# FMC_connector.net
KiCad netlist of a schematic drawn in Altium Designer
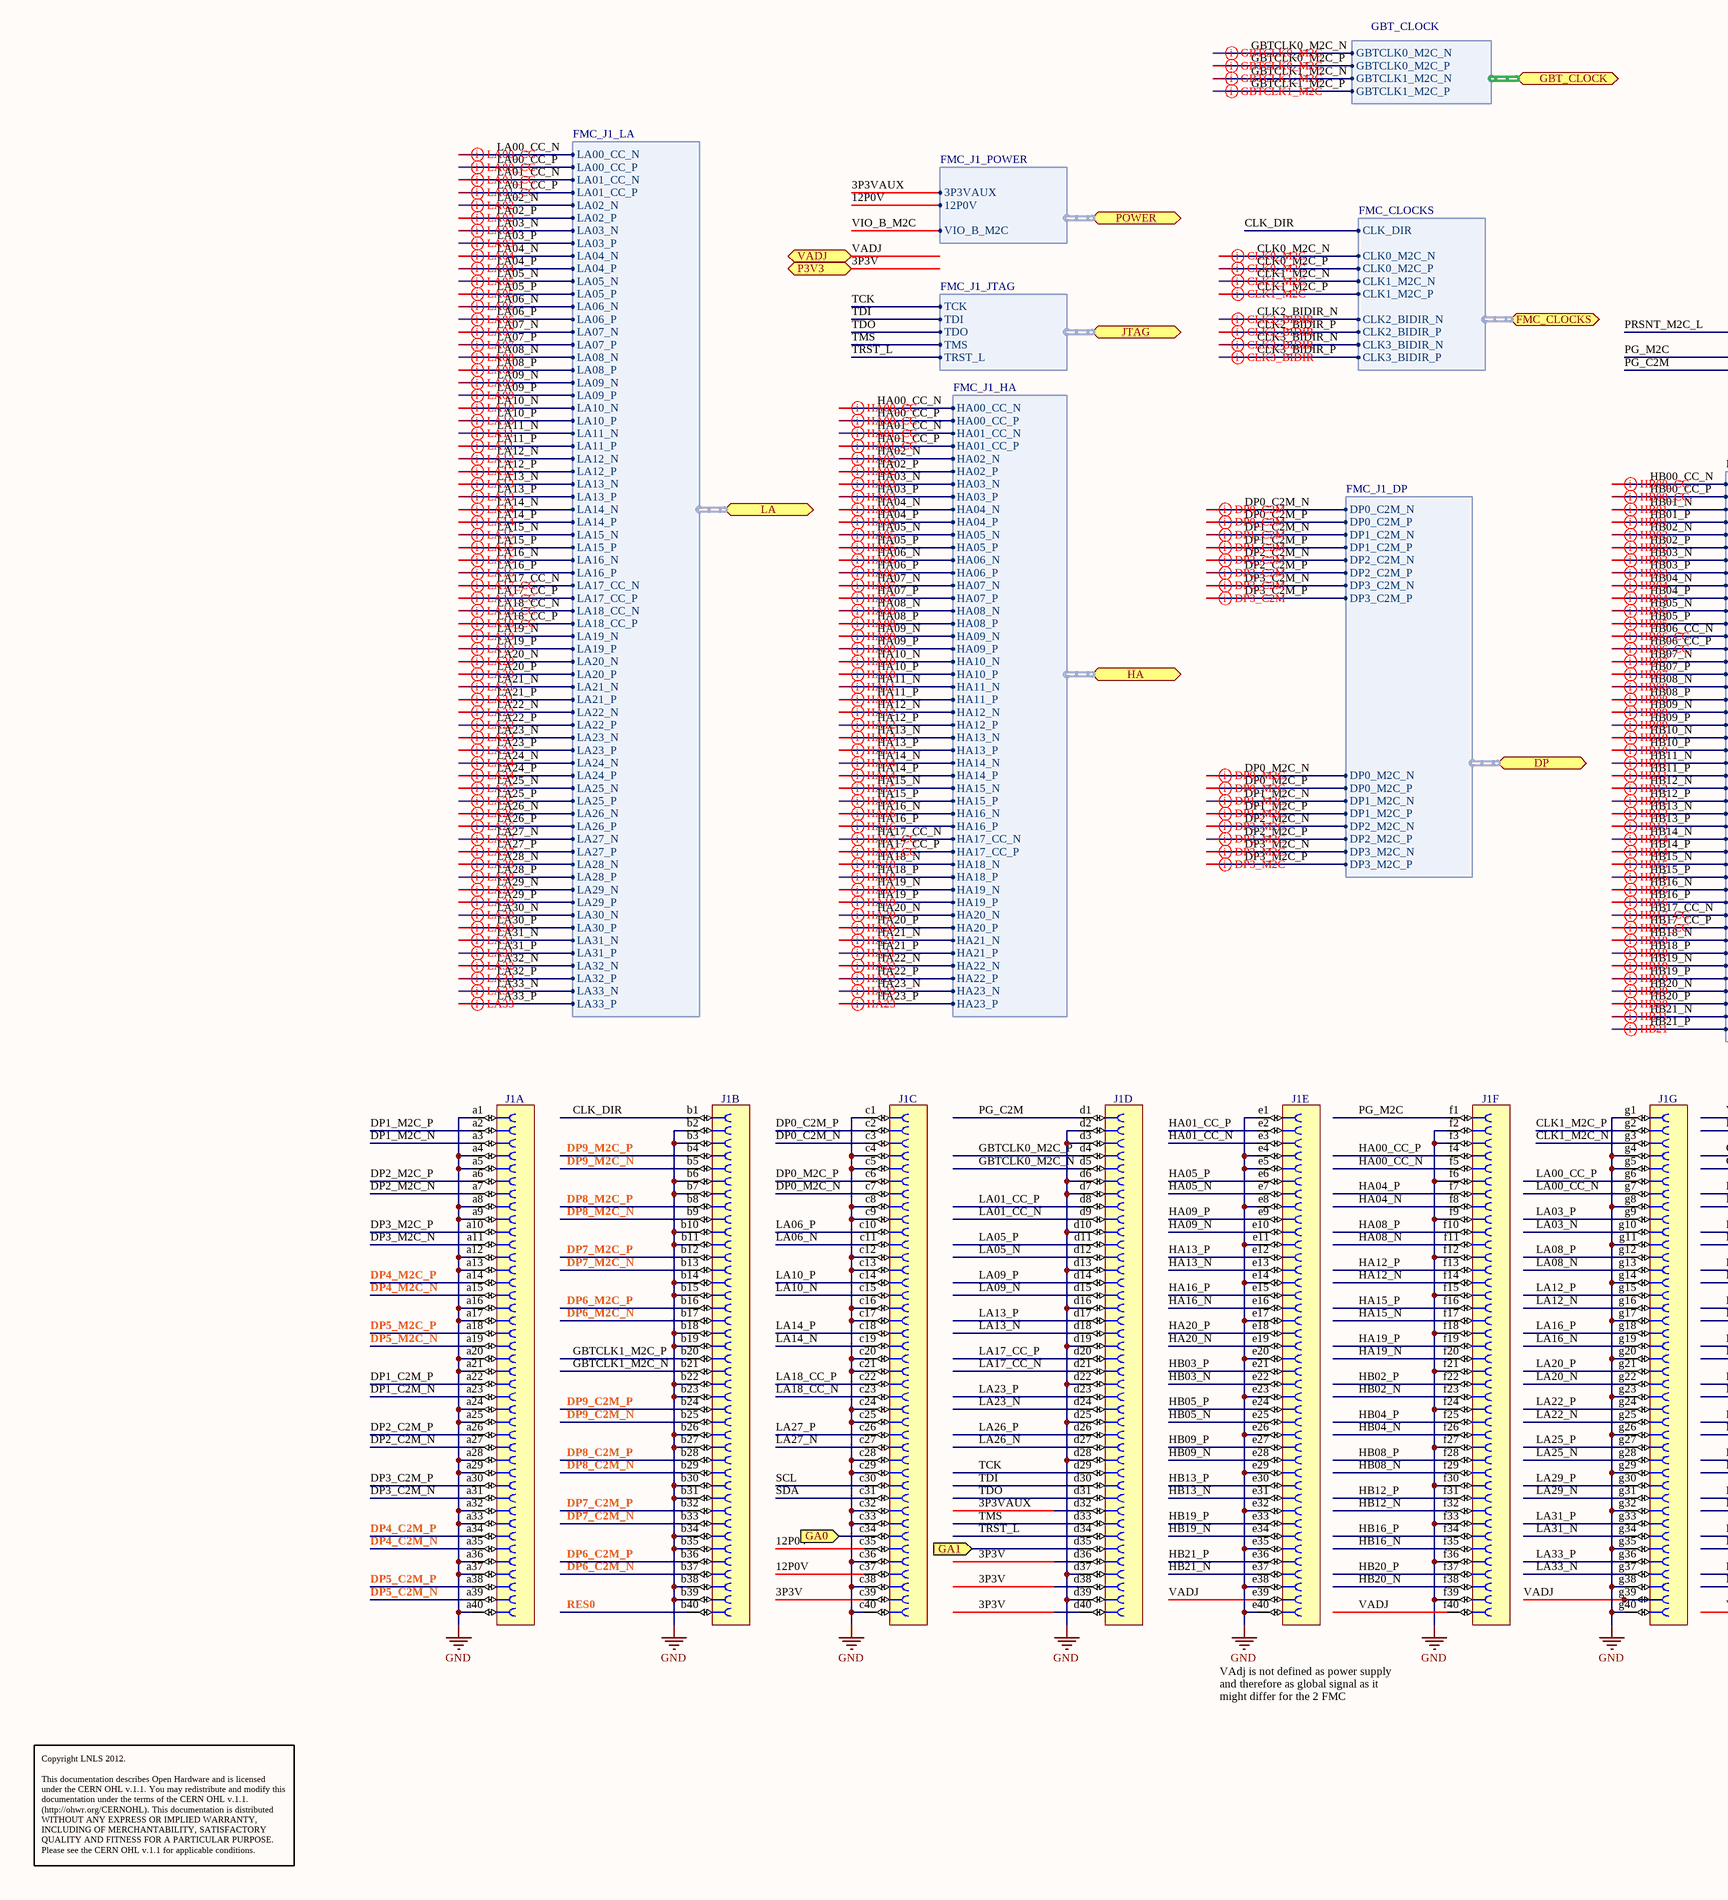
[diagram p0: FMC_connector.SchDoc, left]
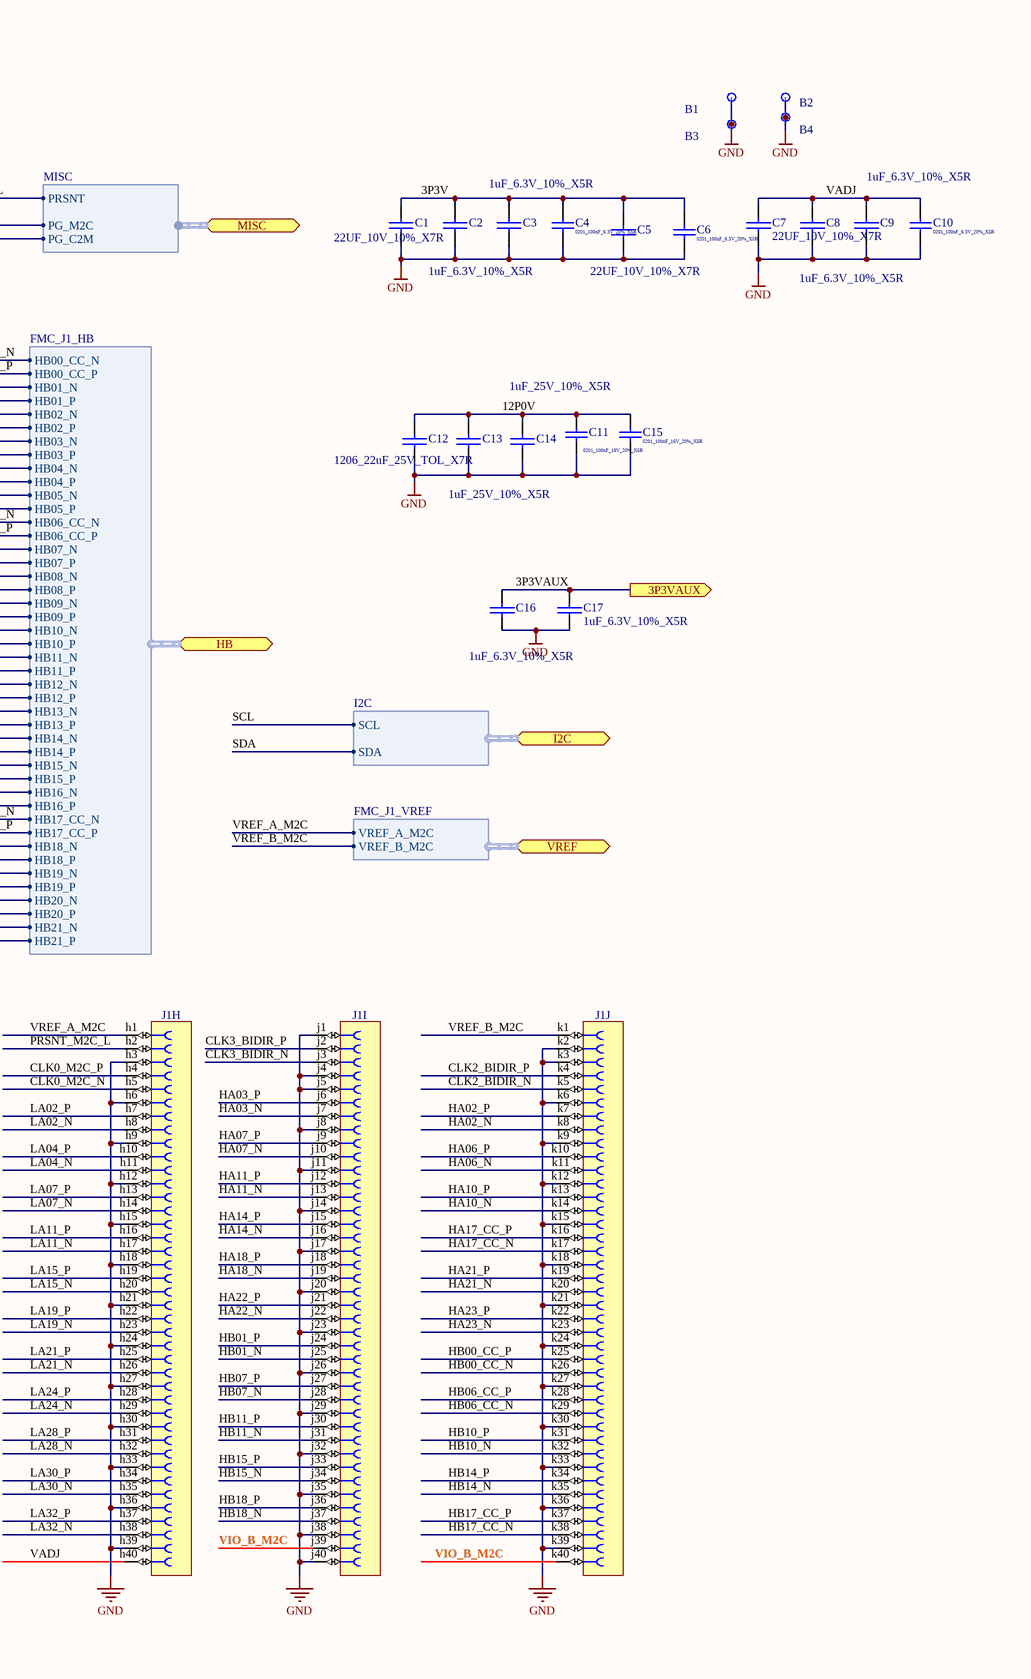
[diagram p1: FMC_connector.SchDoc, right]

(export (version "E")
  (design (tool "Eeschema 10.0.6"))
  (components
    (comp (ref "B1")
      (value "Plated Hole")
      (footprint "MTG270_500")
      (description "Single Terminal Socket")
      (fields (field (name "PART NUMBER") "PLATED_HOLE2.7_PAD5.0") (field (name "AUTHOR") "CERN DEM JMW"))
      (libsource (lib "Eletro-mechanical") (part "Single Terminal Socket"))
    )
    (comp (ref "B2")
      (value "Plated Hole")
      (footprint "MTG270_500")
      (description "Single Terminal Socket")
      (fields (field (name "PART NUMBER") "PLATED_HOLE2.7_PAD5.0") (field (name "AUTHOR") "CERN DEM JMW"))
      (libsource (lib "Eletro-mechanical") (part "Single Terminal Socket"))
    )
    (comp (ref "B3")
      (value "Plated Hole")
      (footprint "MTG270_500")
      (description "Single Terminal Socket")
      (fields (field (name "PART NUMBER") "PLATED_HOLE2.7_PAD5.0") (field (name "AUTHOR") "CERN DEM JMW"))
      (libsource (lib "Eletro-mechanical") (part "Single Terminal Socket"))
    )
    (comp (ref "B4")
      (value "Plated Hole")
      (footprint "MTG270_500")
      (description "Single Terminal Socket")
      (fields (field (name "PART NUMBER") "PLATED_HOLE2.7_PAD5.0") (field (name "AUTHOR") "CERN DEM JMW"))
      (libsource (lib "Eletro-mechanical") (part "Single Terminal Socket"))
    )
    (comp (ref "C1")
      (value "22UF_10V_10%_X7R")
      (footprint "1206C")
      (description "Capacitor SMD")
      (libsource (lib "LIBRARY_SCH") (part "CAP_SMD_1206"))
    )
    (comp (ref "C2")
      (value "1uF_6.3V_10%_X5R")
      (footprint "0603C")
      (description "Capacitor SMD")
      (libsource (lib "LIBRARY_SCH") (part "CAP_SMD_0603"))
    )
    (comp (ref "C3")
      (value "1uF_6.3V_10%_X5R")
      (footprint "0603C")
      (description "Capacitor SMD")
      (libsource (lib "LIBRARY_SCH") (part "CAP_SMD_0603"))
    )
    (comp (ref "C4")
      (value "0201_100nF_6.3V_20%_X5R")
      (footprint "CAPC0603X33N")
      (fields (field (name "PART NUMBER") "Ceramic_0201"))
      (libsource (lib "Capacitors") (part "Capacitor"))
    )
    (comp (ref "C5")
      (value "22UF_10V_10%_X7R")
      (footprint "1206C")
      (description "Capacitor SMD")
      (libsource (lib "LIBRARY_SCH") (part "CAP_SMD_1206"))
    )
    (comp (ref "C6")
      (value "0201_100nF_6.3V_20%_X5R")
      (footprint "CAPC0603X33N")
      (fields (field (name "PART NUMBER") "Ceramic_0201"))
      (libsource (lib "Capacitors") (part "Capacitor"))
    )
    (comp (ref "C7")
      (value "22UF_10V_10%_X7R")
      (footprint "1206C")
      (description "Capacitor SMD")
      (libsource (lib "LIBRARY_SCH") (part "CAP_SMD_1206"))
    )
    (comp (ref "C8")
      (value "1uF_6.3V_10%_X5R")
      (footprint "0603C")
      (description "Capacitor SMD")
      (libsource (lib "LIBRARY_SCH") (part "CAP_SMD_0603"))
    )
    (comp (ref "C9")
      (value "1uF_6.3V_10%_X5R")
      (footprint "0603C")
      (description "Capacitor SMD")
      (libsource (lib "LIBRARY_SCH") (part "CAP_SMD_0603"))
    )
    (comp (ref "C10")
      (value "0201_100nF_6.3V_20%_X5R")
      (footprint "CAPC0603X33N")
      (fields (field (name "PART NUMBER") "Ceramic_0201"))
      (libsource (lib "Capacitors") (part "Capacitor"))
    )
    (comp (ref "C11")
      (value "0201_100nF_16V_20%_X5R")
      (footprint "CAPC0603X33N")
      (fields (field (name "PART NUMBER") "Ceramic_0201"))
      (libsource (lib "Capacitors") (part "Capacitor"))
    )
    (comp (ref "C12")
      (value "1206_22uF_25V_TOL_X7R")
      (footprint "1206C")
      (description "Capacitor SMD")
      (libsource (lib "LIBRARY_SCH") (part "CAP_SMD_1206"))
    )
    (comp (ref "C13")
      (value "1uF_25V_10%_X5R")
      (footprint "0603C")
      (description "Capacitor SMD")
      (libsource (lib "LIBRARY_SCH") (part "CAP_SMD_0603"))
    )
    (comp (ref "C14")
      (value "1uF_25V_10%_X5R")
      (footprint "0603C")
      (description "Capacitor SMD")
      (libsource (lib "LIBRARY_SCH") (part "CAP_SMD_0603"))
    )
    (comp (ref "C15")
      (value "0201_100nF_16V_20%_X5R")
      (footprint "CAPC0603X33N")
      (fields (field (name "PART NUMBER") "Ceramic_0201"))
      (libsource (lib "Capacitors") (part "Capacitor"))
    )
    (comp (ref "C16")
      (value "1uF_6.3V_10%_X5R")
      (footprint "0603C")
      (description "Capacitor SMD")
      (libsource (lib "LIBRARY_SCH") (part "CAP_SMD_0603"))
    )
    (comp (ref "C17")
      (value "1uF_6.3V_10%_X5R")
      (footprint "0603C")
      (description "Capacitor SMD")
      (libsource (lib "LIBRARY_SCH") (part "CAP_SMD_0603"))
    )
    (comp (ref "J1")
      (value "VITA 57")
      (footprint "SAMTEC_ASP-134486-01")
      (description "Connector VITA 57, 400 Female contacts in 10 row abcdefghj")
      (fields
        (field (name "PART NUMBER") "SAMTEC_ASP-134486-01")
        (field (name "MANUFACTURER") "SAMTEC")
        (field (name "AUTHOR") "CERN DEM JLC")
      )
      (libsource (lib "Connectors") (part "Connector VITA 57 400 Female (abcdefghjk)"))
    )
  )
  (nets
    (net (code "12") (name "/3P3V") (class "Default")
      (node (ref "C1") (pin "1") (pinfunction "1_1") (pintype "passive"))
      (node (ref "C2") (pin "1") (pinfunction "1_1") (pintype "passive"))
      (node (ref "C3") (pin "1") (pinfunction "1_1") (pintype "passive"))
      (node (ref "C4") (pin "2") (pinfunction "2_2") (pintype "passive"))
      (node (ref "C5") (pin "1") (pinfunction "1_1") (pintype "passive"))
      (node (ref "C6") (pin "2") (pinfunction "2_2") (pintype "passive"))
      (node (ref "J1") (pin "c39") (pinfunction "c39_c39") (pintype "bidirectional"))
      (node (ref "J1") (pin "d36") (pinfunction "d36_d36") (pintype "bidirectional"))
      (node (ref "J1") (pin "d38") (pinfunction "d38_d38") (pintype "bidirectional"))
      (node (ref "J1") (pin "d40") (pinfunction "d40_d40") (pintype "bidirectional"))
    )
    (net (code "13") (name "/3P3VAUX") (class "Default")
      (node (ref "C16") (pin "1") (pinfunction "1_1") (pintype "passive"))
      (node (ref "C17") (pin "1") (pinfunction "1_1") (pintype "passive"))
      (node (ref "J1") (pin "d32") (pinfunction "d32_d32") (pintype "bidirectional"))
    )
    (net (code "14") (name "/12P0V") (class "Default")
      (node (ref "C11") (pin "2") (pinfunction "2_2") (pintype "passive"))
      (node (ref "C12") (pin "1") (pinfunction "1_1") (pintype "passive"))
      (node (ref "C13") (pin "1") (pinfunction "1_1") (pintype "passive"))
      (node (ref "C14") (pin "1") (pinfunction "1_1") (pintype "passive"))
      (node (ref "C15") (pin "2") (pinfunction "2_2") (pintype "passive"))
      (node (ref "J1") (pin "c35") (pinfunction "c35_c35") (pintype "bidirectional"))
      (node (ref "J1") (pin "c37") (pinfunction "c37_c37") (pintype "bidirectional"))
    )
    (net (code "15") (name "/CLK0_M2C_N") (class "Default")
      (node (ref "J1") (pin "h5") (pinfunction "h5_h5") (pintype "bidirectional"))
    )
    (net (code "16") (name "/CLK0_M2C_P") (class "Default")
      (node (ref "J1") (pin "h4") (pinfunction "h4_h4") (pintype "bidirectional"))
    )
    (net (code "17") (name "/CLK1_M2C_N") (class "Default")
      (node (ref "J1") (pin "g3") (pinfunction "g3_g3") (pintype "bidirectional"))
    )
    (net (code "18") (name "/CLK1_M2C_P") (class "Default")
      (node (ref "J1") (pin "g2") (pinfunction "g2_g2") (pintype "bidirectional"))
    )
    (net (code "19") (name "/CLK2_BIDIR_N") (class "Default")
      (node (ref "J1") (pin "k5") (pinfunction "k5_k5") (pintype "bidirectional"))
    )
    (net (code "20") (name "/CLK2_BIDIR_P") (class "Default")
      (node (ref "J1") (pin "k4") (pinfunction "k4_k4") (pintype "bidirectional"))
    )
    (net (code "21") (name "/CLK3_BIDIR_N") (class "Default")
      (node (ref "J1") (pin "j3") (pinfunction "j3_j3") (pintype "bidirectional"))
    )
    (net (code "22") (name "/CLK3_BIDIR_P") (class "Default")
      (node (ref "J1") (pin "j2") (pinfunction "j2_j2") (pintype "bidirectional"))
    )
    (net (code "23") (name "/CLK_DIR") (class "Default")
      (node (ref "J1") (pin "b1") (pinfunction "b1_b1") (pintype "bidirectional"))
    )
    (net (code "24") (name "/DP0_C2M_N") (class "Default")
      (node (ref "J1") (pin "c3") (pinfunction "c3_c3") (pintype "bidirectional"))
    )
    (net (code "25") (name "/DP0_C2M_P") (class "Default")
      (node (ref "J1") (pin "c2") (pinfunction "c2_c2") (pintype "bidirectional"))
    )
    (net (code "26") (name "/DP0_M2C_N") (class "Default")
      (node (ref "J1") (pin "c7") (pinfunction "c7_c7") (pintype "bidirectional"))
    )
    (net (code "27") (name "/DP0_M2C_P") (class "Default")
      (node (ref "J1") (pin "c6") (pinfunction "c6_c6") (pintype "bidirectional"))
    )
    (net (code "28") (name "/DP1_C2M_N") (class "Default")
      (node (ref "J1") (pin "a23") (pinfunction "a23_a23") (pintype "bidirectional"))
    )
    (net (code "29") (name "/DP1_C2M_P") (class "Default")
      (node (ref "J1") (pin "a22") (pinfunction "a22_a22") (pintype "bidirectional"))
    )
    (net (code "30") (name "/DP1_M2C_N") (class "Default")
      (node (ref "J1") (pin "a3") (pinfunction "a3_a3") (pintype "bidirectional"))
    )
    (net (code "31") (name "/DP1_M2C_P") (class "Default")
      (node (ref "J1") (pin "a2") (pinfunction "a2_a2") (pintype "bidirectional"))
    )
    (net (code "32") (name "/DP2_C2M_N") (class "Default")
      (node (ref "J1") (pin "a27") (pinfunction "a27_a27") (pintype "bidirectional"))
    )
    (net (code "33") (name "/DP2_C2M_P") (class "Default")
      (node (ref "J1") (pin "a26") (pinfunction "a26_a26") (pintype "bidirectional"))
    )
    (net (code "34") (name "/DP2_M2C_N") (class "Default")
      (node (ref "J1") (pin "a7") (pinfunction "a7_a7") (pintype "bidirectional"))
    )
    (net (code "35") (name "/DP2_M2C_P") (class "Default")
      (node (ref "J1") (pin "a6") (pinfunction "a6_a6") (pintype "bidirectional"))
    )
    (net (code "36") (name "/DP3_C2M_N") (class "Default")
      (node (ref "J1") (pin "a31") (pinfunction "a31_a31") (pintype "bidirectional"))
    )
    (net (code "37") (name "/DP3_C2M_P") (class "Default")
      (node (ref "J1") (pin "a30") (pinfunction "a30_a30") (pintype "bidirectional"))
    )
    (net (code "38") (name "/DP3_M2C_N") (class "Default")
      (node (ref "J1") (pin "a11") (pinfunction "a11_a11") (pintype "bidirectional"))
    )
    (net (code "39") (name "/DP3_M2C_P") (class "Default")
      (node (ref "J1") (pin "a10") (pinfunction "a10_a10") (pintype "bidirectional"))
    )
    (net (code "40") (name "/GA0") (class "Default")
      (node (ref "J1") (pin "c34") (pinfunction "c34_c34") (pintype "bidirectional"))
    )
    (net (code "41") (name "/GA1") (class "Default")
      (node (ref "J1") (pin "d35") (pinfunction "d35_d35") (pintype "bidirectional"))
    )
    (net (code "42") (name "/GBTCLK0_M2C_N") (class "Default")
      (node (ref "J1") (pin "d5") (pinfunction "d5_d5") (pintype "bidirectional"))
    )
    (net (code "43") (name "/GBTCLK0_M2C_P") (class "Default")
      (node (ref "J1") (pin "d4") (pinfunction "d4_d4") (pintype "bidirectional"))
    )
    (net (code "44") (name "/GBTCLK1_M2C_N") (class "Default")
      (node (ref "J1") (pin "b21") (pinfunction "b21_b21") (pintype "bidirectional"))
    )
    (net (code "45") (name "/GBTCLK1_M2C_P") (class "Default")
      (node (ref "J1") (pin "b20") (pinfunction "b20_b20") (pintype "bidirectional"))
    )
    (net (code "46") (name "/HA00_CC_N") (class "Default")
      (node (ref "J1") (pin "f5") (pinfunction "f5_f5") (pintype "bidirectional"))
    )
    (net (code "47") (name "/HA00_CC_P") (class "Default")
      (node (ref "J1") (pin "f4") (pinfunction "f4_f4") (pintype "bidirectional"))
    )
    (net (code "48") (name "/HA01_CC_N") (class "Default")
      (node (ref "J1") (pin "e3") (pinfunction "e3_e3") (pintype "bidirectional"))
    )
    (net (code "49") (name "/HA01_CC_P") (class "Default")
      (node (ref "J1") (pin "e2") (pinfunction "e2_e2") (pintype "bidirectional"))
    )
    (net (code "50") (name "/HA02_N") (class "Default")
      (node (ref "J1") (pin "k8") (pinfunction "k8_k8") (pintype "bidirectional"))
    )
    (net (code "51") (name "/HA02_P") (class "Default")
      (node (ref "J1") (pin "k7") (pinfunction "k7_k7") (pintype "bidirectional"))
    )
    (net (code "52") (name "/HA03_N") (class "Default")
      (node (ref "J1") (pin "j7") (pinfunction "j7_j7") (pintype "bidirectional"))
    )
    (net (code "53") (name "/HA03_P") (class "Default")
      (node (ref "J1") (pin "j6") (pinfunction "j6_j6") (pintype "bidirectional"))
    )
    (net (code "54") (name "/HA04_N") (class "Default")
      (node (ref "J1") (pin "f8") (pinfunction "f8_f8") (pintype "bidirectional"))
    )
    (net (code "55") (name "/HA04_P") (class "Default")
      (node (ref "J1") (pin "f7") (pinfunction "f7_f7") (pintype "bidirectional"))
    )
    (net (code "56") (name "/HA05_N") (class "Default")
      (node (ref "J1") (pin "e7") (pinfunction "e7_e7") (pintype "bidirectional"))
    )
    (net (code "57") (name "/HA05_P") (class "Default")
      (node (ref "J1") (pin "e6") (pinfunction "e6_e6") (pintype "bidirectional"))
    )
    (net (code "58") (name "/HA06_N") (class "Default")
      (node (ref "J1") (pin "k11") (pinfunction "k11_k11") (pintype "bidirectional"))
    )
    (net (code "59") (name "/HA06_P") (class "Default")
      (node (ref "J1") (pin "k10") (pinfunction "k10_k10") (pintype "bidirectional"))
    )
    (net (code "60") (name "/HA07_N") (class "Default")
      (node (ref "J1") (pin "j10") (pinfunction "j10_j10") (pintype "bidirectional"))
    )
    (net (code "61") (name "/HA07_P") (class "Default")
      (node (ref "J1") (pin "j9") (pinfunction "j9_j9") (pintype "bidirectional"))
    )
    (net (code "62") (name "/HA08_N") (class "Default")
      (node (ref "J1") (pin "f11") (pinfunction "f11_f11") (pintype "bidirectional"))
    )
    (net (code "63") (name "/HA08_P") (class "Default")
      (node (ref "J1") (pin "f10") (pinfunction "f10_f10") (pintype "bidirectional"))
    )
    (net (code "64") (name "/HA09_N") (class "Default")
      (node (ref "J1") (pin "e10") (pinfunction "e10_e10") (pintype "bidirectional"))
    )
    (net (code "65") (name "/HA09_P") (class "Default")
      (node (ref "J1") (pin "e9") (pinfunction "e9_e9") (pintype "bidirectional"))
    )
    (net (code "66") (name "/HA10_N") (class "Default")
      (node (ref "J1") (pin "k14") (pinfunction "k14_k14") (pintype "bidirectional"))
    )
    (net (code "67") (name "/HA10_P") (class "Default")
      (node (ref "J1") (pin "k13") (pinfunction "k13_k13") (pintype "bidirectional"))
    )
    (net (code "68") (name "/HA11_N") (class "Default")
      (node (ref "J1") (pin "j13") (pinfunction "j13_j13") (pintype "bidirectional"))
    )
    (net (code "69") (name "/HA11_P") (class "Default")
      (node (ref "J1") (pin "j12") (pinfunction "j12_j12") (pintype "bidirectional"))
    )
    (net (code "70") (name "/HA12_N") (class "Default")
      (node (ref "J1") (pin "f14") (pinfunction "f14_f14") (pintype "bidirectional"))
    )
    (net (code "71") (name "/HA12_P") (class "Default")
      (node (ref "J1") (pin "f13") (pinfunction "f13_f13") (pintype "bidirectional"))
    )
    (net (code "72") (name "/HA13_N") (class "Default")
      (node (ref "J1") (pin "e13") (pinfunction "e13_e13") (pintype "bidirectional"))
    )
    (net (code "73") (name "/HA13_P") (class "Default")
      (node (ref "J1") (pin "e12") (pinfunction "e12_e12") (pintype "bidirectional"))
    )
    (net (code "74") (name "/HA14_N") (class "Default")
      (node (ref "J1") (pin "j16") (pinfunction "j16_j16") (pintype "bidirectional"))
    )
    (net (code "75") (name "/HA14_P") (class "Default")
      (node (ref "J1") (pin "j15") (pinfunction "j15_j15") (pintype "bidirectional"))
    )
    (net (code "76") (name "/HA15_N") (class "Default")
      (node (ref "J1") (pin "f17") (pinfunction "f17_f17") (pintype "bidirectional"))
    )
    (net (code "77") (name "/HA15_P") (class "Default")
      (node (ref "J1") (pin "f16") (pinfunction "f16_f16") (pintype "bidirectional"))
    )
    (net (code "78") (name "/HA16_N") (class "Default")
      (node (ref "J1") (pin "e16") (pinfunction "e16_e16") (pintype "bidirectional"))
    )
    (net (code "79") (name "/HA16_P") (class "Default")
      (node (ref "J1") (pin "e15") (pinfunction "e15_e15") (pintype "bidirectional"))
    )
    (net (code "80") (name "/HA17_CC_N") (class "Default")
      (node (ref "J1") (pin "k17") (pinfunction "k17_k17") (pintype "bidirectional"))
    )
    (net (code "81") (name "/HA17_CC_P") (class "Default")
      (node (ref "J1") (pin "k16") (pinfunction "k16_k16") (pintype "bidirectional"))
    )
    (net (code "82") (name "/HA18_N") (class "Default")
      (node (ref "J1") (pin "j19") (pinfunction "j19_j19") (pintype "bidirectional"))
    )
    (net (code "83") (name "/HA18_P") (class "Default")
      (node (ref "J1") (pin "j18") (pinfunction "j18_j18") (pintype "bidirectional"))
    )
    (net (code "84") (name "/HA19_N") (class "Default")
      (node (ref "J1") (pin "f20") (pinfunction "f20_f20") (pintype "bidirectional"))
    )
    (net (code "85") (name "/HA19_P") (class "Default")
      (node (ref "J1") (pin "f19") (pinfunction "f19_f19") (pintype "bidirectional"))
    )
    (net (code "86") (name "/HA20_N") (class "Default")
      (node (ref "J1") (pin "e19") (pinfunction "e19_e19") (pintype "bidirectional"))
    )
    (net (code "87") (name "/HA20_P") (class "Default")
      (node (ref "J1") (pin "e18") (pinfunction "e18_e18") (pintype "bidirectional"))
    )
    (net (code "88") (name "/HA21_N") (class "Default")
      (node (ref "J1") (pin "k20") (pinfunction "k20_k20") (pintype "bidirectional"))
    )
    (net (code "89") (name "/HA21_P") (class "Default")
      (node (ref "J1") (pin "k19") (pinfunction "k19_k19") (pintype "bidirectional"))
    )
    (net (code "90") (name "/HA22_N") (class "Default")
      (node (ref "J1") (pin "j22") (pinfunction "j22_j22") (pintype "bidirectional"))
    )
    (net (code "91") (name "/HA22_P") (class "Default")
      (node (ref "J1") (pin "j21") (pinfunction "j21_j21") (pintype "bidirectional"))
    )
    (net (code "92") (name "/HA23_N") (class "Default")
      (node (ref "J1") (pin "k23") (pinfunction "k23_k23") (pintype "bidirectional"))
    )
    (net (code "93") (name "/HA23_P") (class "Default")
      (node (ref "J1") (pin "k22") (pinfunction "k22_k22") (pintype "bidirectional"))
    )
    (net (code "94") (name "/HB00_CC_N") (class "Default")
      (node (ref "J1") (pin "k26") (pinfunction "k26_k26") (pintype "bidirectional"))
    )
    (net (code "95") (name "/HB00_CC_P") (class "Default")
      (node (ref "J1") (pin "k25") (pinfunction "k25_k25") (pintype "bidirectional"))
    )
    (net (code "96") (name "/HB01_N") (class "Default")
      (node (ref "J1") (pin "j25") (pinfunction "j25_j25") (pintype "bidirectional"))
    )
    (net (code "97") (name "/HB01_P") (class "Default")
      (node (ref "J1") (pin "j24") (pinfunction "j24_j24") (pintype "bidirectional"))
    )
    (net (code "98") (name "/HB02_N") (class "Default")
      (node (ref "J1") (pin "f23") (pinfunction "f23_f23") (pintype "bidirectional"))
    )
    (net (code "99") (name "/HB02_P") (class "Default")
      (node (ref "J1") (pin "f22") (pinfunction "f22_f22") (pintype "bidirectional"))
    )
    (net (code "100") (name "/HB03_N") (class "Default")
      (node (ref "J1") (pin "e22") (pinfunction "e22_e22") (pintype "bidirectional"))
    )
    (net (code "101") (name "/HB03_P") (class "Default")
      (node (ref "J1") (pin "e21") (pinfunction "e21_e21") (pintype "bidirectional"))
    )
    (net (code "102") (name "/HB04_N") (class "Default")
      (node (ref "J1") (pin "f26") (pinfunction "f26_f26") (pintype "bidirectional"))
    )
    (net (code "103") (name "/HB04_P") (class "Default")
      (node (ref "J1") (pin "f25") (pinfunction "f25_f25") (pintype "bidirectional"))
    )
    (net (code "104") (name "/HB05_N") (class "Default")
      (node (ref "J1") (pin "e25") (pinfunction "e25_e25") (pintype "bidirectional"))
    )
    (net (code "105") (name "/HB05_P") (class "Default")
      (node (ref "J1") (pin "e24") (pinfunction "e24_e24") (pintype "bidirectional"))
    )
    (net (code "106") (name "/HB06_CC_N") (class "Default")
      (node (ref "J1") (pin "k29") (pinfunction "k29_k29") (pintype "bidirectional"))
    )
    (net (code "107") (name "/HB06_CC_P") (class "Default")
      (node (ref "J1") (pin "k28") (pinfunction "k28_k28") (pintype "bidirectional"))
    )
    (net (code "108") (name "/HB07_N") (class "Default")
      (node (ref "J1") (pin "j28") (pinfunction "j28_j28") (pintype "bidirectional"))
    )
    (net (code "109") (name "/HB07_P") (class "Default")
      (node (ref "J1") (pin "j27") (pinfunction "j27_j27") (pintype "bidirectional"))
    )
    (net (code "110") (name "/HB08_N") (class "Default")
      (node (ref "J1") (pin "f29") (pinfunction "f29_f29") (pintype "bidirectional"))
    )
    (net (code "111") (name "/HB08_P") (class "Default")
      (node (ref "J1") (pin "f28") (pinfunction "f28_f28") (pintype "bidirectional"))
    )
    (net (code "112") (name "/HB09_N") (class "Default")
      (node (ref "J1") (pin "e28") (pinfunction "e28_e28") (pintype "bidirectional"))
    )
    (net (code "113") (name "/HB09_P") (class "Default")
      (node (ref "J1") (pin "e27") (pinfunction "e27_e27") (pintype "bidirectional"))
    )
    (net (code "114") (name "/HB10_N") (class "Default")
      (node (ref "J1") (pin "k32") (pinfunction "k32_k32") (pintype "bidirectional"))
    )
    (net (code "115") (name "/HB10_P") (class "Default")
      (node (ref "J1") (pin "k31") (pinfunction "k31_k31") (pintype "bidirectional"))
    )
    (net (code "116") (name "/HB11_N") (class "Default")
      (node (ref "J1") (pin "j31") (pinfunction "j31_j31") (pintype "bidirectional"))
    )
    (net (code "117") (name "/HB11_P") (class "Default")
      (node (ref "J1") (pin "j30") (pinfunction "j30_j30") (pintype "bidirectional"))
    )
    (net (code "118") (name "/HB12_N") (class "Default")
      (node (ref "J1") (pin "f32") (pinfunction "f32_f32") (pintype "bidirectional"))
    )
    (net (code "119") (name "/HB12_P") (class "Default")
      (node (ref "J1") (pin "f31") (pinfunction "f31_f31") (pintype "bidirectional"))
    )
    (net (code "120") (name "/HB13_N") (class "Default")
      (node (ref "J1") (pin "e31") (pinfunction "e31_e31") (pintype "bidirectional"))
    )
    (net (code "121") (name "/HB13_P") (class "Default")
      (node (ref "J1") (pin "e30") (pinfunction "e30_e30") (pintype "bidirectional"))
    )
    (net (code "122") (name "/HB14_N") (class "Default")
      (node (ref "J1") (pin "k35") (pinfunction "k35_k35") (pintype "bidirectional"))
    )
    (net (code "123") (name "/HB14_P") (class "Default")
      (node (ref "J1") (pin "k34") (pinfunction "k34_k34") (pintype "bidirectional"))
    )
    (net (code "124") (name "/HB15_N") (class "Default")
      (node (ref "J1") (pin "j34") (pinfunction "j34_j34") (pintype "bidirectional"))
    )
    (net (code "125") (name "/HB15_P") (class "Default")
      (node (ref "J1") (pin "j33") (pinfunction "j33_j33") (pintype "bidirectional"))
    )
    (net (code "126") (name "/HB16_N") (class "Default")
      (node (ref "J1") (pin "f35") (pinfunction "f35_f35") (pintype "bidirectional"))
    )
    (net (code "127") (name "/HB16_P") (class "Default")
      (node (ref "J1") (pin "f34") (pinfunction "f34_f34") (pintype "bidirectional"))
    )
    (net (code "128") (name "/HB17_CC_N") (class "Default")
      (node (ref "J1") (pin "k38") (pinfunction "k38_k38") (pintype "bidirectional"))
    )
    (net (code "129") (name "/HB17_CC_P") (class "Default")
      (node (ref "J1") (pin "k37") (pinfunction "k37_k37") (pintype "bidirectional"))
    )
    (net (code "130") (name "/HB18_N") (class "Default")
      (node (ref "J1") (pin "j37") (pinfunction "j37_j37") (pintype "bidirectional"))
    )
    (net (code "131") (name "/HB18_P") (class "Default")
      (node (ref "J1") (pin "j36") (pinfunction "j36_j36") (pintype "bidirectional"))
    )
    (net (code "132") (name "/HB19_N") (class "Default")
      (node (ref "J1") (pin "e34") (pinfunction "e34_e34") (pintype "bidirectional"))
    )
    (net (code "133") (name "/HB19_P") (class "Default")
      (node (ref "J1") (pin "e33") (pinfunction "e33_e33") (pintype "bidirectional"))
    )
    (net (code "134") (name "/HB20_N") (class "Default")
      (node (ref "J1") (pin "f38") (pinfunction "f38_f38") (pintype "bidirectional"))
    )
    (net (code "135") (name "/HB20_P") (class "Default")
      (node (ref "J1") (pin "f37") (pinfunction "f37_f37") (pintype "bidirectional"))
    )
    (net (code "136") (name "/HB21_N") (class "Default")
      (node (ref "J1") (pin "e37") (pinfunction "e37_e37") (pintype "bidirectional"))
    )
    (net (code "137") (name "/HB21_P") (class "Default")
      (node (ref "J1") (pin "e36") (pinfunction "e36_e36") (pintype "bidirectional"))
    )
    (net (code "138") (name "/LA00_CC_N") (class "Default")
      (node (ref "J1") (pin "g7") (pinfunction "g7_g7") (pintype "bidirectional"))
    )
    (net (code "139") (name "/LA00_CC_P") (class "Default")
      (node (ref "J1") (pin "g6") (pinfunction "g6_g6") (pintype "bidirectional"))
    )
    (net (code "140") (name "/LA01_CC_N") (class "Default")
      (node (ref "J1") (pin "d9") (pinfunction "d9_d9") (pintype "bidirectional"))
    )
    (net (code "141") (name "/LA01_CC_P") (class "Default")
      (node (ref "J1") (pin "d8") (pinfunction "d8_d8") (pintype "bidirectional"))
    )
    (net (code "142") (name "/LA02_N") (class "Default")
      (node (ref "J1") (pin "h8") (pinfunction "h8_h8") (pintype "bidirectional"))
    )
    (net (code "143") (name "/LA02_P") (class "Default")
      (node (ref "J1") (pin "h7") (pinfunction "h7_h7") (pintype "bidirectional"))
    )
    (net (code "144") (name "/LA03_N") (class "Default")
      (node (ref "J1") (pin "g10") (pinfunction "g10_g10") (pintype "bidirectional"))
    )
    (net (code "145") (name "/LA03_P") (class "Default")
      (node (ref "J1") (pin "g9") (pinfunction "g9_g9") (pintype "bidirectional"))
    )
    (net (code "146") (name "/LA04_N") (class "Default")
      (node (ref "J1") (pin "h11") (pinfunction "h11_h11") (pintype "bidirectional"))
    )
    (net (code "147") (name "/LA04_P") (class "Default")
      (node (ref "J1") (pin "h10") (pinfunction "h10_h10") (pintype "bidirectional"))
    )
    (net (code "148") (name "/LA05_N") (class "Default")
      (node (ref "J1") (pin "d12") (pinfunction "d12_d12") (pintype "bidirectional"))
    )
    (net (code "149") (name "/LA05_P") (class "Default")
      (node (ref "J1") (pin "d11") (pinfunction "d11_d11") (pintype "bidirectional"))
    )
    (net (code "150") (name "/LA06_N") (class "Default")
      (node (ref "J1") (pin "c11") (pinfunction "c11_c11") (pintype "bidirectional"))
    )
    (net (code "151") (name "/LA06_P") (class "Default")
      (node (ref "J1") (pin "c10") (pinfunction "c10_c10") (pintype "bidirectional"))
    )
    (net (code "152") (name "/LA07_N") (class "Default")
      (node (ref "J1") (pin "h14") (pinfunction "h14_h14") (pintype "bidirectional"))
    )
    (net (code "153") (name "/LA07_P") (class "Default")
      (node (ref "J1") (pin "h13") (pinfunction "h13_h13") (pintype "bidirectional"))
    )
    (net (code "154") (name "/LA08_N") (class "Default")
      (node (ref "J1") (pin "g13") (pinfunction "g13_g13") (pintype "bidirectional"))
    )
    (net (code "155") (name "/LA08_P") (class "Default")
      (node (ref "J1") (pin "g12") (pinfunction "g12_g12") (pintype "bidirectional"))
    )
    (net (code "156") (name "/LA09_N") (class "Default")
      (node (ref "J1") (pin "d15") (pinfunction "d15_d15") (pintype "bidirectional"))
    )
    (net (code "157") (name "/LA09_P") (class "Default")
      (node (ref "J1") (pin "d14") (pinfunction "d14_d14") (pintype "bidirectional"))
    )
    (net (code "158") (name "/LA10_N") (class "Default")
      (node (ref "J1") (pin "c15") (pinfunction "c15_c15") (pintype "bidirectional"))
    )
    (net (code "159") (name "/LA10_P") (class "Default")
      (node (ref "J1") (pin "c14") (pinfunction "c14_c14") (pintype "bidirectional"))
    )
    (net (code "160") (name "/LA11_N") (class "Default")
      (node (ref "J1") (pin "h17") (pinfunction "h17_h17") (pintype "bidirectional"))
    )
    (net (code "161") (name "/LA11_P") (class "Default")
      (node (ref "J1") (pin "h16") (pinfunction "h16_h16") (pintype "bidirectional"))
    )
    (net (code "162") (name "/LA12_N") (class "Default")
      (node (ref "J1") (pin "g16") (pinfunction "g16_g16") (pintype "bidirectional"))
    )
    (net (code "163") (name "/LA12_P") (class "Default")
      (node (ref "J1") (pin "g15") (pinfunction "g15_g15") (pintype "bidirectional"))
    )
    (net (code "164") (name "/LA13_N") (class "Default")
      (node (ref "J1") (pin "d18") (pinfunction "d18_d18") (pintype "bidirectional"))
    )
    (net (code "165") (name "/LA13_P") (class "Default")
      (node (ref "J1") (pin "d17") (pinfunction "d17_d17") (pintype "bidirectional"))
    )
    (net (code "166") (name "/LA14_N") (class "Default")
      (node (ref "J1") (pin "c19") (pinfunction "c19_c19") (pintype "bidirectional"))
    )
    (net (code "167") (name "/LA14_P") (class "Default")
      (node (ref "J1") (pin "c18") (pinfunction "c18_c18") (pintype "bidirectional"))
    )
    (net (code "168") (name "/LA15_N") (class "Default")
      (node (ref "J1") (pin "h20") (pinfunction "h20_h20") (pintype "bidirectional"))
    )
    (net (code "169") (name "/LA15_P") (class "Default")
      (node (ref "J1") (pin "h19") (pinfunction "h19_h19") (pintype "bidirectional"))
    )
    (net (code "170") (name "/LA16_N") (class "Default")
      (node (ref "J1") (pin "g19") (pinfunction "g19_g19") (pintype "bidirectional"))
    )
    (net (code "171") (name "/LA16_P") (class "Default")
      (node (ref "J1") (pin "g18") (pinfunction "g18_g18") (pintype "bidirectional"))
    )
    (net (code "172") (name "/LA17_CC_N") (class "Default")
      (node (ref "J1") (pin "d21") (pinfunction "d21_d21") (pintype "bidirectional"))
    )
    (net (code "173") (name "/LA17_CC_P") (class "Default")
      (node (ref "J1") (pin "d20") (pinfunction "d20_d20") (pintype "bidirectional"))
    )
    (net (code "174") (name "/LA18_CC_N") (class "Default")
      (node (ref "J1") (pin "c23") (pinfunction "c23_c23") (pintype "bidirectional"))
    )
    (net (code "175") (name "/LA18_CC_P") (class "Default")
      (node (ref "J1") (pin "c22") (pinfunction "c22_c22") (pintype "bidirectional"))
    )
    (net (code "176") (name "/LA19_N") (class "Default")
      (node (ref "J1") (pin "h23") (pinfunction "h23_h23") (pintype "bidirectional"))
    )
    (net (code "177") (name "/LA19_P") (class "Default")
      (node (ref "J1") (pin "h22") (pinfunction "h22_h22") (pintype "bidirectional"))
    )
    (net (code "178") (name "/LA20_N") (class "Default")
      (node (ref "J1") (pin "g22") (pinfunction "g22_g22") (pintype "bidirectional"))
    )
    (net (code "179") (name "/LA20_P") (class "Default")
      (node (ref "J1") (pin "g21") (pinfunction "g21_g21") (pintype "bidirectional"))
    )
    (net (code "180") (name "/LA21_N") (class "Default")
      (node (ref "J1") (pin "h26") (pinfunction "h26_h26") (pintype "bidirectional"))
    )
    (net (code "181") (name "/LA21_P") (class "Default")
      (node (ref "J1") (pin "h25") (pinfunction "h25_h25") (pintype "bidirectional"))
    )
    (net (code "182") (name "/LA22_N") (class "Default")
      (node (ref "J1") (pin "g25") (pinfunction "g25_g25") (pintype "bidirectional"))
    )
    (net (code "183") (name "/LA22_P") (class "Default")
      (node (ref "J1") (pin "g24") (pinfunction "g24_g24") (pintype "bidirectional"))
    )
    (net (code "184") (name "/LA23_N") (class "Default")
      (node (ref "J1") (pin "d24") (pinfunction "d24_d24") (pintype "bidirectional"))
    )
    (net (code "185") (name "/LA23_P") (class "Default")
      (node (ref "J1") (pin "d23") (pinfunction "d23_d23") (pintype "bidirectional"))
    )
    (net (code "186") (name "/LA24_N") (class "Default")
      (node (ref "J1") (pin "h29") (pinfunction "h29_h29") (pintype "bidirectional"))
    )
    (net (code "187") (name "/LA24_P") (class "Default")
      (node (ref "J1") (pin "h28") (pinfunction "h28_h28") (pintype "bidirectional"))
    )
    (net (code "188") (name "/LA25_N") (class "Default")
      (node (ref "J1") (pin "g28") (pinfunction "g28_g28") (pintype "bidirectional"))
    )
    (net (code "189") (name "/LA25_P") (class "Default")
      (node (ref "J1") (pin "g27") (pinfunction "g27_g27") (pintype "bidirectional"))
    )
    (net (code "190") (name "/LA26_N") (class "Default")
      (node (ref "J1") (pin "d27") (pinfunction "d27_d27") (pintype "bidirectional"))
    )
    (net (code "191") (name "/LA26_P") (class "Default")
      (node (ref "J1") (pin "d26") (pinfunction "d26_d26") (pintype "bidirectional"))
    )
    (net (code "192") (name "/LA27_N") (class "Default")
      (node (ref "J1") (pin "c27") (pinfunction "c27_c27") (pintype "bidirectional"))
    )
    (net (code "193") (name "/LA27_P") (class "Default")
      (node (ref "J1") (pin "c26") (pinfunction "c26_c26") (pintype "bidirectional"))
    )
    (net (code "194") (name "/LA28_N") (class "Default")
      (node (ref "J1") (pin "h32") (pinfunction "h32_h32") (pintype "bidirectional"))
    )
    (net (code "195") (name "/LA28_P") (class "Default")
      (node (ref "J1") (pin "h31") (pinfunction "h31_h31") (pintype "bidirectional"))
    )
    (net (code "196") (name "/LA29_N") (class "Default")
      (node (ref "J1") (pin "g31") (pinfunction "g31_g31") (pintype "bidirectional"))
    )
    (net (code "197") (name "/LA29_P") (class "Default")
      (node (ref "J1") (pin "g30") (pinfunction "g30_g30") (pintype "bidirectional"))
    )
    (net (code "198") (name "/LA30_N") (class "Default")
      (node (ref "J1") (pin "h35") (pinfunction "h35_h35") (pintype "bidirectional"))
    )
    (net (code "199") (name "/LA30_P") (class "Default")
      (node (ref "J1") (pin "h34") (pinfunction "h34_h34") (pintype "bidirectional"))
    )
    (net (code "200") (name "/LA31_N") (class "Default")
      (node (ref "J1") (pin "g34") (pinfunction "g34_g34") (pintype "bidirectional"))
    )
    (net (code "201") (name "/LA31_P") (class "Default")
      (node (ref "J1") (pin "g33") (pinfunction "g33_g33") (pintype "bidirectional"))
    )
    (net (code "202") (name "/LA32_N") (class "Default")
      (node (ref "J1") (pin "h38") (pinfunction "h38_h38") (pintype "bidirectional"))
    )
    (net (code "203") (name "/LA32_P") (class "Default")
      (node (ref "J1") (pin "h37") (pinfunction "h37_h37") (pintype "bidirectional"))
    )
    (net (code "204") (name "/LA33_N") (class "Default")
      (node (ref "J1") (pin "g37") (pinfunction "g37_g37") (pintype "bidirectional"))
    )
    (net (code "205") (name "/LA33_P") (class "Default")
      (node (ref "J1") (pin "g36") (pinfunction "g36_g36") (pintype "bidirectional"))
    )
    (net (code "206") (name "/PG_C2M") (class "Default")
      (node (ref "J1") (pin "d1") (pinfunction "d1_d1") (pintype "bidirectional"))
    )
    (net (code "207") (name "/PG_M2C") (class "Default")
      (node (ref "J1") (pin "f1") (pinfunction "f1_f1") (pintype "bidirectional"))
    )
    (net (code "208") (name "/PRSNT_M2C_L") (class "Default")
      (node (ref "J1") (pin "h2") (pinfunction "h2_h2") (pintype "bidirectional"))
    )
    (net (code "209") (name "/SCL") (class "Default")
      (node (ref "J1") (pin "c30") (pinfunction "c30_c30") (pintype "bidirectional"))
    )
    (net (code "210") (name "/SDA") (class "Default")
      (node (ref "J1") (pin "c31") (pinfunction "c31_c31") (pintype "bidirectional"))
    )
    (net (code "211") (name "/TCK") (class "Default")
      (node (ref "J1") (pin "d29") (pinfunction "d29_d29") (pintype "bidirectional"))
    )
    (net (code "212") (name "/TDI") (class "Default")
      (node (ref "J1") (pin "d30") (pinfunction "d30_d30") (pintype "bidirectional"))
    )
    (net (code "213") (name "/TDO") (class "Default")
      (node (ref "J1") (pin "d31") (pinfunction "d31_d31") (pintype "bidirectional"))
    )
    (net (code "214") (name "/TMS") (class "Default")
      (node (ref "J1") (pin "d33") (pinfunction "d33_d33") (pintype "bidirectional"))
    )
    (net (code "215") (name "/TRST_L") (class "Default")
      (node (ref "J1") (pin "d34") (pinfunction "d34_d34") (pintype "bidirectional"))
    )
    (net (code "216") (name "/VADJ") (class "Default")
      (node (ref "C10") (pin "2") (pinfunction "2_2") (pintype "passive"))
      (node (ref "C7") (pin "1") (pinfunction "1_1") (pintype "passive"))
      (node (ref "C8") (pin "1") (pinfunction "1_1") (pintype "passive"))
      (node (ref "C9") (pin "1") (pinfunction "1_1") (pintype "passive"))
      (node (ref "J1") (pin "e39") (pinfunction "e39_e39") (pintype "bidirectional"))
      (node (ref "J1") (pin "f40") (pinfunction "f40_f40") (pintype "bidirectional"))
      (node (ref "J1") (pin "g39") (pinfunction "g39_g39") (pintype "bidirectional"))
      (node (ref "J1") (pin "h40") (pinfunction "h40_h40") (pintype "bidirectional"))
    )
    (net (code "218") (name "/VREF_A_M2C") (class "Default")
      (node (ref "J1") (pin "h1") (pinfunction "h1_h1") (pintype "bidirectional"))
    )
    (net (code "219") (name "/VREF_B_M2C") (class "Default")
      (node (ref "J1") (pin "k1") (pinfunction "k1_k1") (pintype "bidirectional"))
    )
    (net (code "231") (name "GND") (class "Default")
      (node (ref "B1") (pin "1") (pinfunction "1_1") (pintype "bidirectional"))
      (node (ref "B2") (pin "1") (pinfunction "1_1") (pintype "bidirectional"))
      (node (ref "B3") (pin "1") (pinfunction "1_1") (pintype "bidirectional"))
      (node (ref "B4") (pin "1") (pinfunction "1_1") (pintype "bidirectional"))
      (node (ref "C1") (pin "2") (pinfunction "2_2") (pintype "passive"))
      (node (ref "C10") (pin "1") (pinfunction "1_1") (pintype "passive"))
      (node (ref "C11") (pin "1") (pinfunction "1_1") (pintype "passive"))
      (node (ref "C12") (pin "2") (pinfunction "2_2") (pintype "passive"))
      (node (ref "C13") (pin "2") (pinfunction "2_2") (pintype "passive"))
      (node (ref "C14") (pin "2") (pinfunction "2_2") (pintype "passive"))
      (node (ref "C15") (pin "1") (pinfunction "1_1") (pintype "passive"))
      (node (ref "C16") (pin "2") (pinfunction "2_2") (pintype "passive"))
      (node (ref "C17") (pin "2") (pinfunction "2_2") (pintype "passive"))
      (node (ref "C2") (pin "2") (pinfunction "2_2") (pintype "passive"))
      (node (ref "C3") (pin "2") (pinfunction "2_2") (pintype "passive"))
      (node (ref "C4") (pin "1") (pinfunction "1_1") (pintype "passive"))
      (node (ref "C5") (pin "2") (pinfunction "2_2") (pintype "passive"))
      (node (ref "C6") (pin "1") (pinfunction "1_1") (pintype "passive"))
      (node (ref "C7") (pin "2") (pinfunction "2_2") (pintype "passive"))
      (node (ref "C8") (pin "2") (pinfunction "2_2") (pintype "passive"))
      (node (ref "C9") (pin "2") (pinfunction "2_2") (pintype "passive"))
      (node (ref "J1") (pin "a1") (pinfunction "a1_a1") (pintype "bidirectional"))
      (node (ref "J1") (pin "a12") (pinfunction "a12_a12") (pintype "bidirectional"))
      (node (ref "J1") (pin "a13") (pinfunction "a13_a13") (pintype "bidirectional"))
      (node (ref "J1") (pin "a16") (pinfunction "a16_a16") (pintype "bidirectional"))
      (node (ref "J1") (pin "a17") (pinfunction "a17_a17") (pintype "bidirectional"))
      (node (ref "J1") (pin "a20") (pinfunction "a20_a20") (pintype "bidirectional"))
      (node (ref "J1") (pin "a21") (pinfunction "a21_a21") (pintype "bidirectional"))
      (node (ref "J1") (pin "a24") (pinfunction "a24_a24") (pintype "bidirectional"))
      (node (ref "J1") (pin "a25") (pinfunction "a25_a25") (pintype "bidirectional"))
      (node (ref "J1") (pin "a28") (pinfunction "a28_a28") (pintype "bidirectional"))
      (node (ref "J1") (pin "a29") (pinfunction "a29_a29") (pintype "bidirectional"))
      (node (ref "J1") (pin "a32") (pinfunction "a32_a32") (pintype "bidirectional"))
      (node (ref "J1") (pin "a33") (pinfunction "a33_a33") (pintype "bidirectional"))
      (node (ref "J1") (pin "a36") (pinfunction "a36_a36") (pintype "bidirectional"))
      (node (ref "J1") (pin "a37") (pinfunction "a37_a37") (pintype "bidirectional"))
      (node (ref "J1") (pin "a4") (pinfunction "a4_a4") (pintype "bidirectional"))
      (node (ref "J1") (pin "a40") (pinfunction "a40_a40") (pintype "bidirectional"))
      (node (ref "J1") (pin "a5") (pinfunction "a5_a5") (pintype "bidirectional"))
      (node (ref "J1") (pin "a8") (pinfunction "a8_a8") (pintype "bidirectional"))
      (node (ref "J1") (pin "a9") (pinfunction "a9_a9") (pintype "bidirectional"))
      (node (ref "J1") (pin "b10") (pinfunction "b10_b10") (pintype "bidirectional"))
      (node (ref "J1") (pin "b11") (pinfunction "b11_b11") (pintype "bidirectional"))
      (node (ref "J1") (pin "b14") (pinfunction "b14_b14") (pintype "bidirectional"))
      (node (ref "J1") (pin "b15") (pinfunction "b15_b15") (pintype "bidirectional"))
      (node (ref "J1") (pin "b18") (pinfunction "b18_b18") (pintype "bidirectional"))
      (node (ref "J1") (pin "b19") (pinfunction "b19_b19") (pintype "bidirectional"))
      (node (ref "J1") (pin "b2") (pinfunction "b2_b2") (pintype "bidirectional"))
      (node (ref "J1") (pin "b22") (pinfunction "b22_b22") (pintype "bidirectional"))
      (node (ref "J1") (pin "b23") (pinfunction "b23_b23") (pintype "bidirectional"))
      (node (ref "J1") (pin "b26") (pinfunction "b26_b26") (pintype "bidirectional"))
      (node (ref "J1") (pin "b27") (pinfunction "b27_b27") (pintype "bidirectional"))
      (node (ref "J1") (pin "b3") (pinfunction "b3_b3") (pintype "bidirectional"))
      (node (ref "J1") (pin "b30") (pinfunction "b30_b30") (pintype "bidirectional"))
      (node (ref "J1") (pin "b31") (pinfunction "b31_b31") (pintype "bidirectional"))
      (node (ref "J1") (pin "b34") (pinfunction "b34_b34") (pintype "bidirectional"))
      (node (ref "J1") (pin "b35") (pinfunction "b35_b35") (pintype "bidirectional"))
      (node (ref "J1") (pin "b38") (pinfunction "b38_b38") (pintype "bidirectional"))
      (node (ref "J1") (pin "b39") (pinfunction "b39_b39") (pintype "bidirectional"))
      (node (ref "J1") (pin "b6") (pinfunction "b6_b6") (pintype "bidirectional"))
      (node (ref "J1") (pin "b7") (pinfunction "b7_b7") (pintype "bidirectional"))
      (node (ref "J1") (pin "c1") (pinfunction "c1_c1") (pintype "bidirectional"))
      (node (ref "J1") (pin "c12") (pinfunction "c12_c12") (pintype "bidirectional"))
      (node (ref "J1") (pin "c13") (pinfunction "c13_c13") (pintype "bidirectional"))
      (node (ref "J1") (pin "c16") (pinfunction "c16_c16") (pintype "bidirectional"))
      (node (ref "J1") (pin "c17") (pinfunction "c17_c17") (pintype "bidirectional"))
      (node (ref "J1") (pin "c20") (pinfunction "c20_c20") (pintype "bidirectional"))
      (node (ref "J1") (pin "c21") (pinfunction "c21_c21") (pintype "bidirectional"))
      (node (ref "J1") (pin "c24") (pinfunction "c24_c24") (pintype "bidirectional"))
      (node (ref "J1") (pin "c25") (pinfunction "c25_c25") (pintype "bidirectional"))
      (node (ref "J1") (pin "c28") (pinfunction "c28_c28") (pintype "bidirectional"))
      (node (ref "J1") (pin "c29") (pinfunction "c29_c29") (pintype "bidirectional"))
      (node (ref "J1") (pin "c32") (pinfunction "c32_c32") (pintype "bidirectional"))
      (node (ref "J1") (pin "c33") (pinfunction "c33_c33") (pintype "bidirectional"))
      (node (ref "J1") (pin "c36") (pinfunction "c36_c36") (pintype "bidirectional"))
      (node (ref "J1") (pin "c38") (pinfunction "c38_c38") (pintype "bidirectional"))
      (node (ref "J1") (pin "c4") (pinfunction "c4_c4") (pintype "bidirectional"))
      (node (ref "J1") (pin "c40") (pinfunction "c40_c40") (pintype "bidirectional"))
      (node (ref "J1") (pin "c5") (pinfunction "c5_c5") (pintype "bidirectional"))
      (node (ref "J1") (pin "c8") (pinfunction "c8_c8") (pintype "bidirectional"))
      (node (ref "J1") (pin "c9") (pinfunction "c9_c9") (pintype "bidirectional"))
      (node (ref "J1") (pin "d10") (pinfunction "d10_d10") (pintype "bidirectional"))
      (node (ref "J1") (pin "d13") (pinfunction "d13_d13") (pintype "bidirectional"))
      (node (ref "J1") (pin "d16") (pinfunction "d16_d16") (pintype "bidirectional"))
      (node (ref "J1") (pin "d19") (pinfunction "d19_d19") (pintype "bidirectional"))
      (node (ref "J1") (pin "d2") (pinfunction "d2_d2") (pintype "bidirectional"))
      (node (ref "J1") (pin "d22") (pinfunction "d22_d22") (pintype "bidirectional"))
      (node (ref "J1") (pin "d25") (pinfunction "d25_d25") (pintype "bidirectional"))
      (node (ref "J1") (pin "d28") (pinfunction "d28_d28") (pintype "bidirectional"))
      (node (ref "J1") (pin "d3") (pinfunction "d3_d3") (pintype "bidirectional"))
      (node (ref "J1") (pin "d37") (pinfunction "d37_d37") (pintype "bidirectional"))
      (node (ref "J1") (pin "d39") (pinfunction "d39_d39") (pintype "bidirectional"))
      (node (ref "J1") (pin "d6") (pinfunction "d6_d6") (pintype "bidirectional"))
      (node (ref "J1") (pin "d7") (pinfunction "d7_d7") (pintype "bidirectional"))
      (node (ref "J1") (pin "e1") (pinfunction "e1_e1") (pintype "bidirectional"))
      (node (ref "J1") (pin "e11") (pinfunction "e11_e11") (pintype "bidirectional"))
      (node (ref "J1") (pin "e14") (pinfunction "e14_e14") (pintype "bidirectional"))
      (node (ref "J1") (pin "e17") (pinfunction "e17_e17") (pintype "bidirectional"))
      (node (ref "J1") (pin "e20") (pinfunction "e20_e20") (pintype "bidirectional"))
      (node (ref "J1") (pin "e23") (pinfunction "e23_e23") (pintype "bidirectional"))
      (node (ref "J1") (pin "e26") (pinfunction "e26_e26") (pintype "bidirectional"))
      (node (ref "J1") (pin "e29") (pinfunction "e29_e29") (pintype "bidirectional"))
      (node (ref "J1") (pin "e32") (pinfunction "e32_e32") (pintype "bidirectional"))
      (node (ref "J1") (pin "e35") (pinfunction "e35_e35") (pintype "bidirectional"))
      (node (ref "J1") (pin "e38") (pinfunction "e38_e38") (pintype "bidirectional"))
      (node (ref "J1") (pin "e4") (pinfunction "e4_e4") (pintype "bidirectional"))
      (node (ref "J1") (pin "e40") (pinfunction "e40_e40") (pintype "bidirectional"))
      (node (ref "J1") (pin "e5") (pinfunction "e5_e5") (pintype "bidirectional"))
      (node (ref "J1") (pin "e8") (pinfunction "e8_e8") (pintype "bidirectional"))
      (node (ref "J1") (pin "f12") (pinfunction "f12_f12") (pintype "bidirectional"))
      (node (ref "J1") (pin "f15") (pinfunction "f15_f15") (pintype "bidirectional"))
      (node (ref "J1") (pin "f18") (pinfunction "f18_f18") (pintype "bidirectional"))
      (node (ref "J1") (pin "f2") (pinfunction "f2_f2") (pintype "bidirectional"))
      (node (ref "J1") (pin "f21") (pinfunction "f21_f21") (pintype "bidirectional"))
      (node (ref "J1") (pin "f24") (pinfunction "f24_f24") (pintype "bidirectional"))
      (node (ref "J1") (pin "f27") (pinfunction "f27_f27") (pintype "bidirectional"))
      (node (ref "J1") (pin "f3") (pinfunction "f3_f3") (pintype "bidirectional"))
      (node (ref "J1") (pin "f30") (pinfunction "f30_f30") (pintype "bidirectional"))
      (node (ref "J1") (pin "f33") (pinfunction "f33_f33") (pintype "bidirectional"))
      (node (ref "J1") (pin "f36") (pinfunction "f36_f36") (pintype "bidirectional"))
      (node (ref "J1") (pin "f39") (pinfunction "f39_f39") (pintype "bidirectional"))
      (node (ref "J1") (pin "f6") (pinfunction "f6_f6") (pintype "bidirectional"))
      (node (ref "J1") (pin "f9") (pinfunction "f9_f9") (pintype "bidirectional"))
      (node (ref "J1") (pin "g1") (pinfunction "g1_g1") (pintype "bidirectional"))
      (node (ref "J1") (pin "g11") (pinfunction "g11_g11") (pintype "bidirectional"))
      (node (ref "J1") (pin "g14") (pinfunction "g14_g14") (pintype "bidirectional"))
      (node (ref "J1") (pin "g17") (pinfunction "g17_g17") (pintype "bidirectional"))
      (node (ref "J1") (pin "g20") (pinfunction "g20_g20") (pintype "bidirectional"))
      (node (ref "J1") (pin "g23") (pinfunction "g23_g23") (pintype "bidirectional"))
      (node (ref "J1") (pin "g26") (pinfunction "g26_g26") (pintype "bidirectional"))
      (node (ref "J1") (pin "g29") (pinfunction "g29_g29") (pintype "bidirectional"))
      (node (ref "J1") (pin "g32") (pinfunction "g32_g32") (pintype "bidirectional"))
      (node (ref "J1") (pin "g35") (pinfunction "g35_g35") (pintype "bidirectional"))
      (node (ref "J1") (pin "g38") (pinfunction "g38_g38") (pintype "bidirectional"))
      (node (ref "J1") (pin "g4") (pinfunction "g4_g4") (pintype "bidirectional"))
      (node (ref "J1") (pin "g40") (pinfunction "g40_g40") (pintype "bidirectional"))
      (node (ref "J1") (pin "g5") (pinfunction "g5_g5") (pintype "bidirectional"))
      (node (ref "J1") (pin "g8") (pinfunction "g8_g8") (pintype "bidirectional"))
      (node (ref "J1") (pin "h12") (pinfunction "h12_h12") (pintype "bidirectional"))
      (node (ref "J1") (pin "h15") (pinfunction "h15_h15") (pintype "bidirectional"))
      (node (ref "J1") (pin "h18") (pinfunction "h18_h18") (pintype "bidirectional"))
      (node (ref "J1") (pin "h21") (pinfunction "h21_h21") (pintype "bidirectional"))
      (node (ref "J1") (pin "h24") (pinfunction "h24_h24") (pintype "bidirectional"))
      (node (ref "J1") (pin "h27") (pinfunction "h27_h27") (pintype "bidirectional"))
      (node (ref "J1") (pin "h3") (pinfunction "h3_h3") (pintype "bidirectional"))
      (node (ref "J1") (pin "h30") (pinfunction "h30_h30") (pintype "bidirectional"))
      (node (ref "J1") (pin "h33") (pinfunction "h33_h33") (pintype "bidirectional"))
      (node (ref "J1") (pin "h36") (pinfunction "h36_h36") (pintype "bidirectional"))
      (node (ref "J1") (pin "h39") (pinfunction "h39_h39") (pintype "bidirectional"))
      (node (ref "J1") (pin "h6") (pinfunction "h6_h6") (pintype "bidirectional"))
      (node (ref "J1") (pin "h9") (pinfunction "h9_h9") (pintype "bidirectional"))
      (node (ref "J1") (pin "j1") (pinfunction "j1_j1") (pintype "bidirectional"))
      (node (ref "J1") (pin "j11") (pinfunction "j11_j11") (pintype "bidirectional"))
      (node (ref "J1") (pin "j14") (pinfunction "j14_j14") (pintype "bidirectional"))
      (node (ref "J1") (pin "j17") (pinfunction "j17_j17") (pintype "bidirectional"))
      (node (ref "J1") (pin "j20") (pinfunction "j20_j20") (pintype "bidirectional"))
      (node (ref "J1") (pin "j23") (pinfunction "j23_j23") (pintype "bidirectional"))
      (node (ref "J1") (pin "j26") (pinfunction "j26_j26") (pintype "bidirectional"))
      (node (ref "J1") (pin "j29") (pinfunction "j29_j29") (pintype "bidirectional"))
      (node (ref "J1") (pin "j32") (pinfunction "j32_j32") (pintype "bidirectional"))
      (node (ref "J1") (pin "j35") (pinfunction "j35_j35") (pintype "bidirectional"))
      (node (ref "J1") (pin "j38") (pinfunction "j38_j38") (pintype "bidirectional"))
      (node (ref "J1") (pin "j4") (pinfunction "j4_j4") (pintype "bidirectional"))
      (node (ref "J1") (pin "j40") (pinfunction "j40_j40") (pintype "bidirectional"))
      (node (ref "J1") (pin "j5") (pinfunction "j5_j5") (pintype "bidirectional"))
      (node (ref "J1") (pin "j8") (pinfunction "j8_j8") (pintype "bidirectional"))
      (node (ref "J1") (pin "k12") (pinfunction "k12_k12") (pintype "bidirectional"))
      (node (ref "J1") (pin "k15") (pinfunction "k15_k15") (pintype "bidirectional"))
      (node (ref "J1") (pin "k18") (pinfunction "k18_k18") (pintype "bidirectional"))
      (node (ref "J1") (pin "k2") (pinfunction "k2_k2") (pintype "bidirectional"))
      (node (ref "J1") (pin "k21") (pinfunction "k21_k21") (pintype "bidirectional"))
      (node (ref "J1") (pin "k24") (pinfunction "k24_k24") (pintype "bidirectional"))
      (node (ref "J1") (pin "k27") (pinfunction "k27_k27") (pintype "bidirectional"))
      (node (ref "J1") (pin "k3") (pinfunction "k3_k3") (pintype "bidirectional"))
      (node (ref "J1") (pin "k30") (pinfunction "k30_k30") (pintype "bidirectional"))
      (node (ref "J1") (pin "k33") (pinfunction "k33_k33") (pintype "bidirectional"))
      (node (ref "J1") (pin "k36") (pinfunction "k36_k36") (pintype "bidirectional"))
      (node (ref "J1") (pin "k39") (pinfunction "k39_k39") (pintype "bidirectional"))
      (node (ref "J1") (pin "k6") (pinfunction "k6_k6") (pintype "bidirectional"))
      (node (ref "J1") (pin "k9") (pinfunction "k9_k9") (pintype "bidirectional"))
    )
    (net (code "232") (name "unconnected-(J1-Pada14)") (class "Default")
      (node (ref "J1") (pin "a14") (pinfunction "a14_a14") (pintype "bidirectional"))
    )
    (net (code "233") (name "unconnected-(J1-Pada15)") (class "Default")
      (node (ref "J1") (pin "a15") (pinfunction "a15_a15") (pintype "bidirectional"))
    )
    (net (code "234") (name "unconnected-(J1-Pada18)") (class "Default")
      (node (ref "J1") (pin "a18") (pinfunction "a18_a18") (pintype "bidirectional"))
    )
    (net (code "235") (name "unconnected-(J1-Pada19)") (class "Default")
      (node (ref "J1") (pin "a19") (pinfunction "a19_a19") (pintype "bidirectional"))
    )
    (net (code "236") (name "unconnected-(J1-Pada34)") (class "Default")
      (node (ref "J1") (pin "a34") (pinfunction "a34_a34") (pintype "bidirectional"))
    )
    (net (code "237") (name "unconnected-(J1-Pada35)") (class "Default")
      (node (ref "J1") (pin "a35") (pinfunction "a35_a35") (pintype "bidirectional"))
    )
    (net (code "238") (name "unconnected-(J1-Pada38)") (class "Default")
      (node (ref "J1") (pin "a38") (pinfunction "a38_a38") (pintype "bidirectional"))
    )
    (net (code "239") (name "unconnected-(J1-Pada39)") (class "Default")
      (node (ref "J1") (pin "a39") (pinfunction "a39_a39") (pintype "bidirectional"))
    )
    (net (code "240") (name "unconnected-(J1-Padb4)") (class "Default")
      (node (ref "J1") (pin "b4") (pinfunction "b4_b4") (pintype "bidirectional"))
    )
    (net (code "241") (name "unconnected-(J1-Padb5)") (class "Default")
      (node (ref "J1") (pin "b5") (pinfunction "b5_b5") (pintype "bidirectional"))
    )
    (net (code "242") (name "unconnected-(J1-Padb8)") (class "Default")
      (node (ref "J1") (pin "b8") (pinfunction "b8_b8") (pintype "bidirectional"))
    )
    (net (code "243") (name "unconnected-(J1-Padb9)") (class "Default")
      (node (ref "J1") (pin "b9") (pinfunction "b9_b9") (pintype "bidirectional"))
    )
    (net (code "244") (name "unconnected-(J1-Padb12)") (class "Default")
      (node (ref "J1") (pin "b12") (pinfunction "b12_b12") (pintype "bidirectional"))
    )
    (net (code "245") (name "unconnected-(J1-Padb13)") (class "Default")
      (node (ref "J1") (pin "b13") (pinfunction "b13_b13") (pintype "bidirectional"))
    )
    (net (code "246") (name "unconnected-(J1-Padb16)") (class "Default")
      (node (ref "J1") (pin "b16") (pinfunction "b16_b16") (pintype "bidirectional"))
    )
    (net (code "247") (name "unconnected-(J1-Padb17)") (class "Default")
      (node (ref "J1") (pin "b17") (pinfunction "b17_b17") (pintype "bidirectional"))
    )
    (net (code "248") (name "unconnected-(J1-Padb24)") (class "Default")
      (node (ref "J1") (pin "b24") (pinfunction "b24_b24") (pintype "bidirectional"))
    )
    (net (code "249") (name "unconnected-(J1-Padb25)") (class "Default")
      (node (ref "J1") (pin "b25") (pinfunction "b25_b25") (pintype "bidirectional"))
    )
    (net (code "250") (name "unconnected-(J1-Padb28)") (class "Default")
      (node (ref "J1") (pin "b28") (pinfunction "b28_b28") (pintype "bidirectional"))
    )
    (net (code "251") (name "unconnected-(J1-Padb29)") (class "Default")
      (node (ref "J1") (pin "b29") (pinfunction "b29_b29") (pintype "bidirectional"))
    )
    (net (code "252") (name "unconnected-(J1-Padb32)") (class "Default")
      (node (ref "J1") (pin "b32") (pinfunction "b32_b32") (pintype "bidirectional"))
    )
    (net (code "253") (name "unconnected-(J1-Padb33)") (class "Default")
      (node (ref "J1") (pin "b33") (pinfunction "b33_b33") (pintype "bidirectional"))
    )
    (net (code "254") (name "unconnected-(J1-Padb36)") (class "Default")
      (node (ref "J1") (pin "b36") (pinfunction "b36_b36") (pintype "bidirectional"))
    )
    (net (code "255") (name "unconnected-(J1-Padb37)") (class "Default")
      (node (ref "J1") (pin "b37") (pinfunction "b37_b37") (pintype "bidirectional"))
    )
    (net (code "256") (name "unconnected-(J1-Padb40)") (class "Default")
      (node (ref "J1") (pin "b40") (pinfunction "b40_b40") (pintype "bidirectional"))
    )
    (net (code "257") (name "unconnected-(J1-Padj39)") (class "Default")
      (node (ref "J1") (pin "j39") (pinfunction "j39_j39") (pintype "bidirectional"))
    )
    (net (code "258") (name "unconnected-(J1-Padk40)") (class "Default")
      (node (ref "J1") (pin "k40") (pinfunction "k40_k40") (pintype "bidirectional"))
    )
  )
)
